# aprs.net
KiCad netlist of a schematic drawn in EAGLE
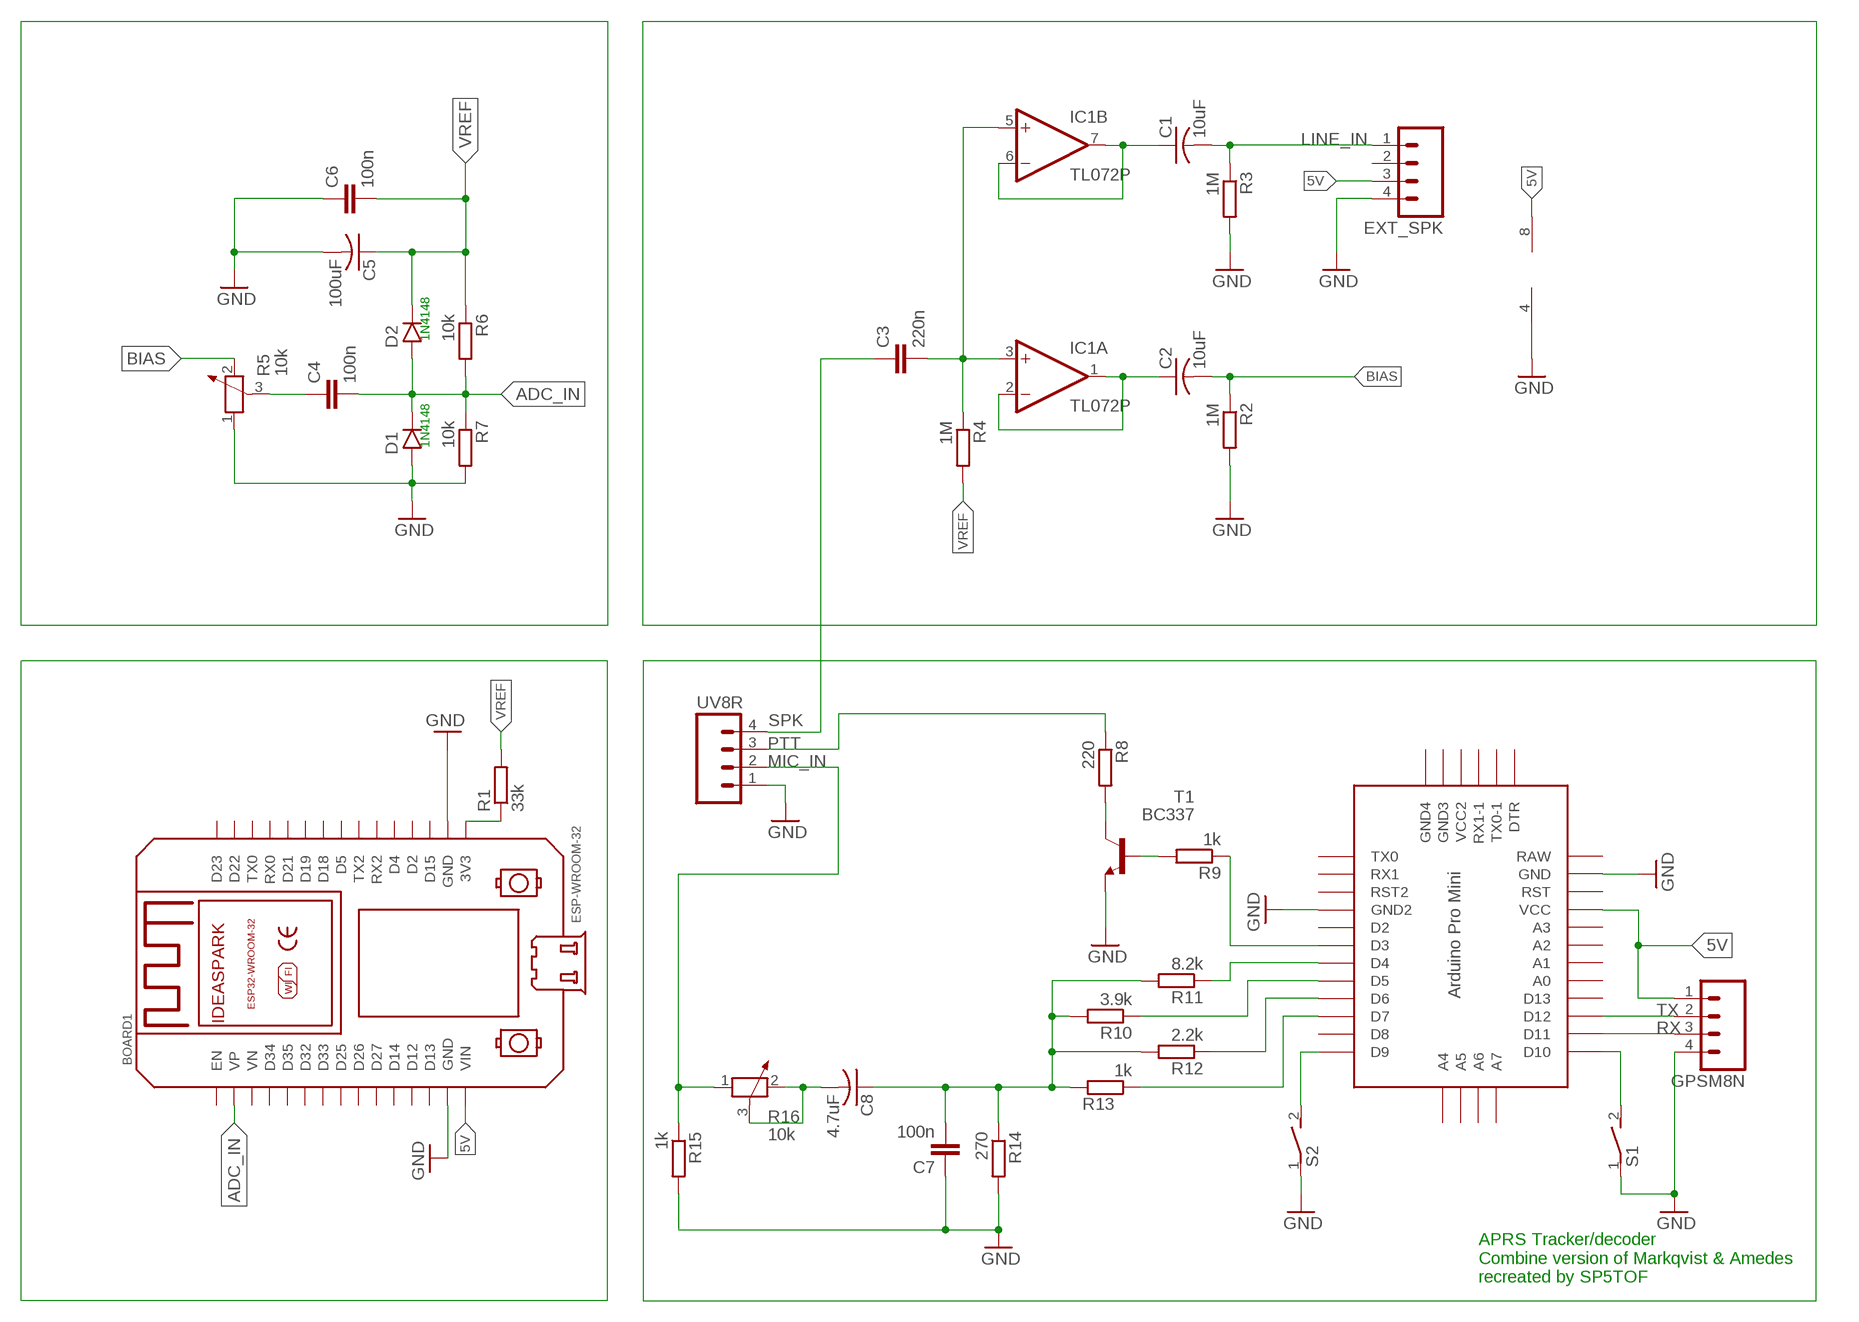
[diagram p0: schematic, sheet 1]

(export (version "E")
  (design (tool "Eeschema 10.0.6"))
  (components
    (comp (ref "BOARD1")
      (value "ESP32DEVKITV1")
      (footprint "eagle-import:ESP32-DEVKITV1")
      (libsource (lib "eagle-import") (part "ESP32DEVKITV1"))
    )
    (comp (ref "C1")
      (value "10uF")
      (footprint "eagle-import:C050-035X075")
      (libsource (lib "eagle-import") (part "C-US050-035X075"))
    )
    (comp (ref "C2")
      (value "10uF")
      (footprint "eagle-import:C050-035X075")
      (libsource (lib "eagle-import") (part "C-US050-035X075"))
    )
    (comp (ref "C3")
      (value "220n")
      (footprint "eagle-import:C025-025X050")
      (libsource (lib "eagle-import") (part "C-EU025-025X050"))
    )
    (comp (ref "C4")
      (value "100n")
      (footprint "eagle-import:C025-025X050")
      (libsource (lib "eagle-import") (part "C-EU025-025X050"))
    )
    (comp (ref "C5")
      (value "100uF")
      (footprint "eagle-import:C050-035X075")
      (libsource (lib "eagle-import") (part "C-US050-035X075"))
    )
    (comp (ref "C6")
      (value "100n")
      (footprint "eagle-import:C025-025X050")
      (libsource (lib "eagle-import") (part "C-EU025-025X050"))
    )
    (comp (ref "C7")
      (value "100n")
      (footprint "eagle-import:C025-025X050")
      (libsource (lib "eagle-import") (part "C-EU025-025X050"))
    )
    (comp (ref "C8")
      (value "4.7uF")
      (footprint "eagle-import:C050-035X075")
      (libsource (lib "eagle-import") (part "C-US050-035X075"))
    )
    (comp (ref "D1")
      (value "1N4148-3")
      (footprint "eagle-import:DO35-3")
      (libsource (lib "eagle-import") (part "1N4148-3"))
    )
    (comp (ref "D2")
      (value "1N4148-3")
      (footprint "eagle-import:DO35-3")
      (libsource (lib "eagle-import") (part "1N4148-3"))
    )
    (comp (ref "EXT_SPK")
      (value "M04")
      (footprint "eagle-import:04P")
      (libsource (lib "eagle-import") (part "M04"))
    )
    (comp (ref "GPSM8N")
      (value "M04")
      (footprint "eagle-import:04P")
      (libsource (lib "eagle-import") (part "M04"))
    )
    (comp (ref "IC1")
      (value "TL072P")
      (footprint "eagle-import:DIL08")
      (libsource (lib "eagle-import") (part "TL072P"))
    )
    (comp (ref "R1")
      (value "33k")
      (footprint "eagle-import:0207_7")
      (libsource (lib "eagle-import") (part "R-EU_0207/7"))
    )
    (comp (ref "R2")
      (value "1M")
      (footprint "eagle-import:0207_7")
      (libsource (lib "eagle-import") (part "R-EU_0207/7"))
    )
    (comp (ref "R3")
      (value "1M")
      (footprint "eagle-import:0207_7")
      (libsource (lib "eagle-import") (part "R-EU_0207/7"))
    )
    (comp (ref "R4")
      (value "1M")
      (footprint "eagle-import:0207_7")
      (libsource (lib "eagle-import") (part "R-EU_0207/7"))
    )
    (comp (ref "R5")
      (value "10k")
      (footprint "eagle-import:PT-10S")
      (libsource (lib "eagle-import") (part "POTENTIOMETER_PT-10S"))
    )
    (comp (ref "R6")
      (value "10k")
      (footprint "eagle-import:0207_7")
      (libsource (lib "eagle-import") (part "R-EU_0207/7"))
    )
    (comp (ref "R7")
      (value "10k")
      (footprint "eagle-import:0207_7")
      (libsource (lib "eagle-import") (part "R-EU_0207/7"))
    )
    (comp (ref "R8")
      (value "220")
      (footprint "eagle-import:0207_7")
      (libsource (lib "eagle-import") (part "R-EU_0207/7"))
    )
    (comp (ref "R9")
      (value "1k")
      (footprint "eagle-import:0207_7")
      (libsource (lib "eagle-import") (part "R-EU_0207/7"))
    )
    (comp (ref "R10")
      (value "3.9k")
      (footprint "eagle-import:0207_7")
      (libsource (lib "eagle-import") (part "R-EU_0207/7"))
    )
    (comp (ref "R11")
      (value "8.2k")
      (footprint "eagle-import:0207_7")
      (libsource (lib "eagle-import") (part "R-EU_0207/7"))
    )
    (comp (ref "R12")
      (value "2.2k")
      (footprint "eagle-import:0207_7")
      (libsource (lib "eagle-import") (part "R-EU_0207/7"))
    )
    (comp (ref "R13")
      (value "1k")
      (footprint "eagle-import:0207_7")
      (libsource (lib "eagle-import") (part "R-EU_0207/7"))
    )
    (comp (ref "R14")
      (value "270")
      (footprint "eagle-import:0207_7")
      (libsource (lib "eagle-import") (part "R-EU_0207/7"))
    )
    (comp (ref "R15")
      (value "1k")
      (footprint "eagle-import:0207_7")
      (libsource (lib "eagle-import") (part "R-EU_0207/7"))
    )
    (comp (ref "R16")
      (value "10k")
      (footprint "eagle-import:PT-10S")
      (libsource (lib "eagle-import") (part "POTENTIOMETER_PT-10S"))
    )
    (comp (ref "S1")
      (value "DS01E")
      (footprint "eagle-import:DS-01")
      (libsource (lib "eagle-import") (part "DS01E"))
    )
    (comp (ref "S2")
      (value "DS01E")
      (footprint "eagle-import:DS-01")
      (libsource (lib "eagle-import") (part "DS01E"))
    )
    (comp (ref "T1")
      (value "BC337")
      (footprint "eagle-import:TO92")
      (libsource (lib "eagle-import") (part "BC337"))
    )
    (comp (ref "U$1")
      (value "PRO-MINI")
      (footprint "eagle-import:PRO-MINI")
      (libsource (lib "eagle-import") (part "PRO-MINI"))
    )
    (comp (ref "UV8R")
      (value "M04")
      (footprint "eagle-import:04P")
      (libsource (lib "eagle-import") (part "M04"))
    )
  )
  (nets
    (net (code "1") (name "/LINE_IN") (class "Default")
      (node (ref "C1") (pin "2") (pinfunction "2_2") (pintype "passive"))
      (node (ref "EXT_SPK") (pin "1") (pinfunction "1_1") (pintype "passive"))
      (node (ref "R3") (pin "1") (pinfunction "1_1") (pintype "passive"))
    )
    (net (code "2") (name "/MIC_IN") (class "Default")
      (node (ref "R15") (pin "1") (pinfunction "1_1") (pintype "passive"))
      (node (ref "R16") (pin "1") (pinfunction "1_1") (pintype "passive"))
      (node (ref "UV8R") (pin "2") (pinfunction "2_2") (pintype "passive"))
    )
    (net (code "3") (name "/PTT") (class "Default")
      (node (ref "R8") (pin "1") (pinfunction "1_1") (pintype "passive"))
      (node (ref "UV8R") (pin "3") (pinfunction "3_3") (pintype "passive"))
    )
    (net (code "4") (name "/RAW") (class "Default")
      (node (ref "U$1") (pin "RAW") (pinfunction "RAW_RAW") (pintype "power_in"))
    )
    (net (code "5") (name "/RX") (class "Default")
      (node (ref "GPSM8N") (pin "3") (pinfunction "3_3") (pintype "passive"))
      (node (ref "U$1") (pin "D11") (pinfunction "D11_D11") (pintype "bidirectional"))
    )
    (net (code "6") (name "/SPK") (class "Default")
      (node (ref "C3") (pin "1") (pinfunction "1_1") (pintype "passive"))
      (node (ref "UV8R") (pin "4") (pinfunction "4_4") (pintype "passive"))
    )
    (net (code "7") (name "/TX") (class "Default")
      (node (ref "GPSM8N") (pin "2") (pinfunction "2_2") (pintype "passive"))
      (node (ref "U$1") (pin "D12") (pinfunction "D12_D12") (pintype "bidirectional"))
    )
    (net (code "8") (name "5V") (class "Default")
      (node (ref "BOARD1") (pin "VIN") (pinfunction "VIN_VIN") (pintype "bidirectional"))
      (node (ref "EXT_SPK") (pin "3") (pinfunction "3_3") (pintype "passive"))
      (node (ref "GPSM8N") (pin "1") (pinfunction "1_1") (pintype "passive"))
      (node (ref "IC1") (pin "8") (pinfunction "V+_8") (pintype "power_in"))
      (node (ref "U$1") (pin "VCC") (pinfunction "VCC_VCC") (pintype "bidirectional"))
    )
    (net (code "9") (name "ADC_IN") (class "Default")
      (node (ref "BOARD1") (pin "VP") (pinfunction "VP_VP") (pintype "bidirectional"))
      (node (ref "C4") (pin "2") (pinfunction "2_2") (pintype "passive"))
      (node (ref "D1") (pin "C") (pinfunction "C_C") (pintype "passive"))
      (node (ref "D2") (pin "A") (pinfunction "A_A") (pintype "passive"))
      (node (ref "R6") (pin "2") (pinfunction "2_2") (pintype "passive"))
      (node (ref "R7") (pin "1") (pinfunction "1_1") (pintype "passive"))
    )
    (net (code "10") (name "BIAS") (class "Default")
      (node (ref "C2") (pin "2") (pinfunction "2_2") (pintype "passive"))
      (node (ref "R2") (pin "1") (pinfunction "1_1") (pintype "passive"))
      (node (ref "R5") (pin "2") (pinfunction "2_2") (pintype "passive"))
    )
    (net (code "11") (name "GND") (class "Default")
      (node (ref "BOARD1") (pin "GND") (pinfunction "GND_GND") (pintype "bidirectional"))
      (node (ref "BOARD1") (pin "GND@1") (pinfunction "GND_GND@1") (pintype "bidirectional"))
      (node (ref "C5") (pin "2") (pinfunction "2_2") (pintype "passive"))
      (node (ref "C6") (pin "1") (pinfunction "1_1") (pintype "passive"))
      (node (ref "C7") (pin "1") (pinfunction "1_1") (pintype "passive"))
      (node (ref "D1") (pin "A") (pinfunction "A_A") (pintype "passive"))
      (node (ref "EXT_SPK") (pin "4") (pinfunction "4_4") (pintype "passive"))
      (node (ref "GPSM8N") (pin "4") (pinfunction "4_4") (pintype "passive"))
      (node (ref "IC1") (pin "4") (pinfunction "V-_4") (pintype "power_in"))
      (node (ref "R14") (pin "2") (pinfunction "2_2") (pintype "passive"))
      (node (ref "R15") (pin "2") (pinfunction "2_2") (pintype "passive"))
      (node (ref "R2") (pin "2") (pinfunction "2_2") (pintype "passive"))
      (node (ref "R3") (pin "2") (pinfunction "2_2") (pintype "passive"))
      (node (ref "R5") (pin "1") (pinfunction "1_1") (pintype "passive"))
      (node (ref "R7") (pin "2") (pinfunction "2_2") (pintype "passive"))
      (node (ref "S1") (pin "1") (pinfunction "1_1") (pintype "passive"))
      (node (ref "S2") (pin "1") (pinfunction "1_1") (pintype "passive"))
      (node (ref "T1") (pin "1") (pinfunction "E_1") (pintype "passive"))
      (node (ref "U$1") (pin "GND") (pinfunction "GND_GND") (pintype "input"))
      (node (ref "U$1") (pin "GND1") (pinfunction "GND2_GND1") (pintype "bidirectional"))
      (node (ref "UV8R") (pin "1") (pinfunction "1_1") (pintype "passive"))
    )
    (net (code "12") (name "Net-(BOARD1-Pad3V3)") (class "Default")
      (node (ref "BOARD1") (pin "3V3") (pinfunction "3V3_3V3") (pintype "bidirectional"))
      (node (ref "R1") (pin "1") (pinfunction "1_1") (pintype "passive"))
    )
    (net (code "13") (name "Net-(C4-Pad1)") (class "Default")
      (node (ref "C4") (pin "1") (pinfunction "1_1") (pintype "passive"))
      (node (ref "R5") (pin "3") (pinfunction "3_3") (pintype "passive"))
    )
    (net (code "14") (name "Net-(C7-Pad2)") (class "Default")
      (node (ref "C7") (pin "2") (pinfunction "2_2") (pintype "passive"))
      (node (ref "C8") (pin "1") (pinfunction "1_1") (pintype "passive"))
      (node (ref "R10") (pin "2") (pinfunction "2_2") (pintype "passive"))
      (node (ref "R11") (pin "2") (pinfunction "2_2") (pintype "passive"))
      (node (ref "R12") (pin "2") (pinfunction "2_2") (pintype "passive"))
      (node (ref "R13") (pin "2") (pinfunction "2_2") (pintype "passive"))
      (node (ref "R14") (pin "1") (pinfunction "1_1") (pintype "passive"))
    )
    (net (code "15") (name "Net-(C8-Pad2)") (class "Default")
      (node (ref "C8") (pin "2") (pinfunction "2_2") (pintype "passive"))
      (node (ref "R16") (pin "2") (pinfunction "2_2") (pintype "passive"))
      (node (ref "R16") (pin "3") (pinfunction "3_3") (pintype "passive"))
    )
    (net (code "16") (name "Net-(IC1A-+IN)") (class "Default")
      (node (ref "C3") (pin "2") (pinfunction "2_2") (pintype "passive"))
      (node (ref "IC1") (pin "3") (pinfunction "+IN_3") (pintype "input"))
      (node (ref "IC1") (pin "5") (pinfunction "+IN_5") (pintype "input"))
      (node (ref "R4") (pin "1") (pinfunction "1_1") (pintype "passive"))
    )
    (net (code "17") (name "Net-(IC1A--IN)") (class "Default")
      (node (ref "C2") (pin "1") (pinfunction "1_1") (pintype "passive"))
      (node (ref "IC1") (pin "1") (pinfunction "OUT_1") (pintype "output"))
      (node (ref "IC1") (pin "2") (pinfunction "-IN_2") (pintype "input"))
    )
    (net (code "18") (name "Net-(IC1B--IN)") (class "Default")
      (node (ref "C1") (pin "1") (pinfunction "1_1") (pintype "passive"))
      (node (ref "IC1") (pin "6") (pinfunction "-IN_6") (pintype "input"))
      (node (ref "IC1") (pin "7") (pinfunction "OUT_7") (pintype "output"))
    )
    (net (code "19") (name "Net-(R9-Pad1)") (class "Default")
      (node (ref "R9") (pin "1") (pinfunction "1_1") (pintype "passive"))
      (node (ref "U$1") (pin "D3") (pinfunction "D3_D3") (pintype "bidirectional"))
    )
    (net (code "20") (name "Net-(R10-Pad1)") (class "Default")
      (node (ref "R10") (pin "1") (pinfunction "1_1") (pintype "passive"))
      (node (ref "U$1") (pin "D5") (pinfunction "D5_D5") (pintype "bidirectional"))
    )
    (net (code "21") (name "Net-(R11-Pad1)") (class "Default")
      (node (ref "R11") (pin "1") (pinfunction "1_1") (pintype "passive"))
      (node (ref "U$1") (pin "D4") (pinfunction "D4_D4") (pintype "bidirectional"))
    )
    (net (code "22") (name "Net-(R12-Pad1)") (class "Default")
      (node (ref "R12") (pin "1") (pinfunction "1_1") (pintype "passive"))
      (node (ref "U$1") (pin "D6") (pinfunction "D6_D6") (pintype "bidirectional"))
    )
    (net (code "23") (name "Net-(R13-Pad1)") (class "Default")
      (node (ref "R13") (pin "1") (pinfunction "1_1") (pintype "passive"))
      (node (ref "U$1") (pin "D7") (pinfunction "D7_D7") (pintype "bidirectional"))
    )
    (net (code "24") (name "Net-(S1-Pad2)") (class "Default")
      (node (ref "S1") (pin "2") (pinfunction "2_2") (pintype "passive"))
      (node (ref "U$1") (pin "D10") (pinfunction "D10_D10") (pintype "bidirectional"))
    )
    (net (code "25") (name "Net-(S2-Pad2)") (class "Default")
      (node (ref "S2") (pin "2") (pinfunction "2_2") (pintype "passive"))
      (node (ref "U$1") (pin "D9") (pinfunction "D9_D9") (pintype "bidirectional"))
    )
    (net (code "26") (name "Net-(T1-B)") (class "Default")
      (node (ref "R9") (pin "2") (pinfunction "2_2") (pintype "passive"))
      (node (ref "T1") (pin "2") (pinfunction "B_2") (pintype "passive"))
    )
    (net (code "27") (name "Net-(T1-C)") (class "Default")
      (node (ref "R8") (pin "2") (pinfunction "2_2") (pintype "passive"))
      (node (ref "T1") (pin "3") (pinfunction "C_3") (pintype "passive"))
    )
    (net (code "28") (name "VREF") (class "Default")
      (node (ref "C5") (pin "1") (pinfunction "1_1") (pintype "passive"))
      (node (ref "C6") (pin "2") (pinfunction "2_2") (pintype "passive"))
      (node (ref "D2") (pin "C") (pinfunction "C_C") (pintype "passive"))
      (node (ref "R1") (pin "2") (pinfunction "2_2") (pintype "passive"))
      (node (ref "R4") (pin "2") (pinfunction "2_2") (pintype "passive"))
      (node (ref "R6") (pin "1") (pinfunction "1_1") (pintype "passive"))
    )
    (net (code "29") (name "unconnected-(BOARD1-PadD2)") (class "Default")
      (node (ref "BOARD1") (pin "D2") (pinfunction "D2_D2") (pintype "bidirectional"))
    )
    (net (code "30") (name "unconnected-(BOARD1-PadD4)") (class "Default")
      (node (ref "BOARD1") (pin "D4") (pinfunction "D4_D4") (pintype "bidirectional"))
    )
    (net (code "31") (name "unconnected-(BOARD1-PadD5)") (class "Default")
      (node (ref "BOARD1") (pin "D5") (pinfunction "D5_D5") (pintype "bidirectional"))
    )
    (net (code "32") (name "unconnected-(BOARD1-PadD12)") (class "Default")
      (node (ref "BOARD1") (pin "D12") (pinfunction "D12_D12") (pintype "bidirectional"))
    )
    (net (code "33") (name "unconnected-(BOARD1-PadD13)") (class "Default")
      (node (ref "BOARD1") (pin "D13") (pinfunction "D13_D13") (pintype "bidirectional"))
    )
    (net (code "34") (name "unconnected-(BOARD1-PadD14)") (class "Default")
      (node (ref "BOARD1") (pin "D14") (pinfunction "D14_D14") (pintype "bidirectional"))
    )
    (net (code "35") (name "unconnected-(BOARD1-PadD15)") (class "Default")
      (node (ref "BOARD1") (pin "D15") (pinfunction "D15_D15") (pintype "bidirectional"))
    )
    (net (code "36") (name "unconnected-(BOARD1-PadD18)") (class "Default")
      (node (ref "BOARD1") (pin "D18") (pinfunction "D18_D18") (pintype "bidirectional"))
    )
    (net (code "37") (name "unconnected-(BOARD1-PadD19)") (class "Default")
      (node (ref "BOARD1") (pin "D19") (pinfunction "D19_D19") (pintype "bidirectional"))
    )
    (net (code "38") (name "unconnected-(BOARD1-PadD21)") (class "Default")
      (node (ref "BOARD1") (pin "D21") (pinfunction "D21_D21") (pintype "bidirectional"))
    )
    (net (code "39") (name "unconnected-(BOARD1-PadD22)") (class "Default")
      (node (ref "BOARD1") (pin "D22") (pinfunction "D22_D22") (pintype "bidirectional"))
    )
    (net (code "40") (name "unconnected-(BOARD1-PadD23)") (class "Default")
      (node (ref "BOARD1") (pin "D23") (pinfunction "D23_D23") (pintype "bidirectional"))
    )
    (net (code "41") (name "unconnected-(BOARD1-PadD25)") (class "Default")
      (node (ref "BOARD1") (pin "D25") (pinfunction "D25_D25") (pintype "bidirectional"))
    )
    (net (code "42") (name "unconnected-(BOARD1-PadD26)") (class "Default")
      (node (ref "BOARD1") (pin "D26") (pinfunction "D26_D26") (pintype "bidirectional"))
    )
    (net (code "43") (name "unconnected-(BOARD1-PadD27)") (class "Default")
      (node (ref "BOARD1") (pin "D27") (pinfunction "D27_D27") (pintype "bidirectional"))
    )
    (net (code "44") (name "unconnected-(BOARD1-PadD32)") (class "Default")
      (node (ref "BOARD1") (pin "D32") (pinfunction "D32_D32") (pintype "bidirectional"))
    )
    (net (code "45") (name "unconnected-(BOARD1-PadD33)") (class "Default")
      (node (ref "BOARD1") (pin "D33") (pinfunction "D33_D33") (pintype "bidirectional"))
    )
    (net (code "46") (name "unconnected-(BOARD1-PadD34)") (class "Default")
      (node (ref "BOARD1") (pin "D34") (pinfunction "D34_D34") (pintype "bidirectional"))
    )
    (net (code "47") (name "unconnected-(BOARD1-PadD35)") (class "Default")
      (node (ref "BOARD1") (pin "D35") (pinfunction "D35_D35") (pintype "bidirectional"))
    )
    (net (code "48") (name "unconnected-(BOARD1-PadEN)") (class "Default")
      (node (ref "BOARD1") (pin "EN") (pinfunction "EN_EN") (pintype "bidirectional"))
    )
    (net (code "49") (name "unconnected-(BOARD1-PadRX0)") (class "Default")
      (node (ref "BOARD1") (pin "RX0") (pinfunction "RX0_RX0") (pintype "bidirectional"))
    )
    (net (code "50") (name "unconnected-(BOARD1-PadRX2)") (class "Default")
      (node (ref "BOARD1") (pin "RX2") (pinfunction "RX2_RX2") (pintype "bidirectional"))
    )
    (net (code "51") (name "unconnected-(BOARD1-PadTX0)") (class "Default")
      (node (ref "BOARD1") (pin "TX0") (pinfunction "TX0_TX0") (pintype "bidirectional"))
    )
    (net (code "52") (name "unconnected-(BOARD1-PadTX2)") (class "Default")
      (node (ref "BOARD1") (pin "TX2") (pinfunction "TX2_TX2") (pintype "bidirectional"))
    )
    (net (code "53") (name "unconnected-(BOARD1-PadVN)") (class "Default")
      (node (ref "BOARD1") (pin "VN") (pinfunction "VN_VN") (pintype "bidirectional"))
    )
    (net (code "54") (name "unconnected-(EXT_SPK-Pad2)") (class "Default")
      (node (ref "EXT_SPK") (pin "2") (pinfunction "2_2") (pintype "passive"))
    )
    (net (code "55") (name "unconnected-(U$1-GND4-PadGND2)") (class "Default")
      (node (ref "U$1") (pin "GND2") (pinfunction "GND4_GND2") (pintype "bidirectional"))
    )
    (net (code "56") (name "unconnected-(U$1-PadA0)") (class "Default")
      (node (ref "U$1") (pin "A0") (pinfunction "A0_A0") (pintype "bidirectional"))
    )
    (net (code "57") (name "unconnected-(U$1-PadA1)") (class "Default")
      (node (ref "U$1") (pin "A1") (pinfunction "A1_A1") (pintype "bidirectional"))
    )
    (net (code "58") (name "unconnected-(U$1-PadA2)") (class "Default")
      (node (ref "U$1") (pin "A2") (pinfunction "A2_A2") (pintype "bidirectional"))
    )
    (net (code "59") (name "unconnected-(U$1-PadA3)") (class "Default")
      (node (ref "U$1") (pin "A3") (pinfunction "A3_A3") (pintype "bidirectional"))
    )
    (net (code "60") (name "unconnected-(U$1-PadA4)") (class "Default")
      (node (ref "U$1") (pin "A4") (pinfunction "A4_A4") (pintype "bidirectional"))
    )
    (net (code "61") (name "unconnected-(U$1-PadA5)") (class "Default")
      (node (ref "U$1") (pin "A5") (pinfunction "A5_A5") (pintype "bidirectional"))
    )
    (net (code "62") (name "unconnected-(U$1-PadA6)") (class "Default")
      (node (ref "U$1") (pin "A6") (pinfunction "A6_A6") (pintype "bidirectional"))
    )
    (net (code "63") (name "unconnected-(U$1-PadA7)") (class "Default")
      (node (ref "U$1") (pin "A7") (pinfunction "A7_A7") (pintype "bidirectional"))
    )
    (net (code "64") (name "unconnected-(U$1-PadD2)") (class "Default")
      (node (ref "U$1") (pin "D2") (pinfunction "D2_D2") (pintype "bidirectional"))
    )
    (net (code "65") (name "unconnected-(U$1-PadD8)") (class "Default")
      (node (ref "U$1") (pin "D8") (pinfunction "D8_D8") (pintype "bidirectional"))
    )
    (net (code "66") (name "unconnected-(U$1-PadD13)") (class "Default")
      (node (ref "U$1") (pin "D13") (pinfunction "D13_D13") (pintype "bidirectional"))
    )
    (net (code "67") (name "unconnected-(U$1-PadDTR)") (class "Default")
      (node (ref "U$1") (pin "DTR") (pinfunction "DTR_DTR") (pintype "bidirectional"))
    )
    (net (code "68") (name "unconnected-(U$1-PadGND3)") (class "Default")
      (node (ref "U$1") (pin "GND3") (pinfunction "GND3_GND3") (pintype "bidirectional"))
    )
    (net (code "69") (name "unconnected-(U$1-PadRST)") (class "Default")
      (node (ref "U$1") (pin "RST") (pinfunction "RST_RST") (pintype "bidirectional"))
    )
    (net (code "70") (name "unconnected-(U$1-PadRX1)") (class "Default")
      (node (ref "U$1") (pin "RX1") (pinfunction "RX1_RX1") (pintype "bidirectional"))
    )
    (net (code "71") (name "unconnected-(U$1-PadRX1-1)") (class "Default")
      (node (ref "U$1") (pin "RX1-1") (pinfunction "RX1-1_RX1-1") (pintype "bidirectional"))
    )
    (net (code "72") (name "unconnected-(U$1-PadTX0)") (class "Default")
      (node (ref "U$1") (pin "TX0") (pinfunction "TX0_TX0") (pintype "bidirectional"))
    )
    (net (code "73") (name "unconnected-(U$1-PadTX0-1)") (class "Default")
      (node (ref "U$1") (pin "TX0-1") (pinfunction "TX0-1_TX0-1") (pintype "bidirectional"))
    )
    (net (code "74") (name "unconnected-(U$1-RST2-PadRST1)") (class "Default")
      (node (ref "U$1") (pin "RST1") (pinfunction "RST2_RST1") (pintype "bidirectional"))
    )
    (net (code "75") (name "unconnected-(U$1-VCC2-PadVCC1)") (class "Default")
      (node (ref "U$1") (pin "VCC1") (pinfunction "VCC2_VCC1") (pintype "bidirectional"))
    )
  )
)
